# soldering.net
KiCad netlist of a schematic drawn in Altium Designer
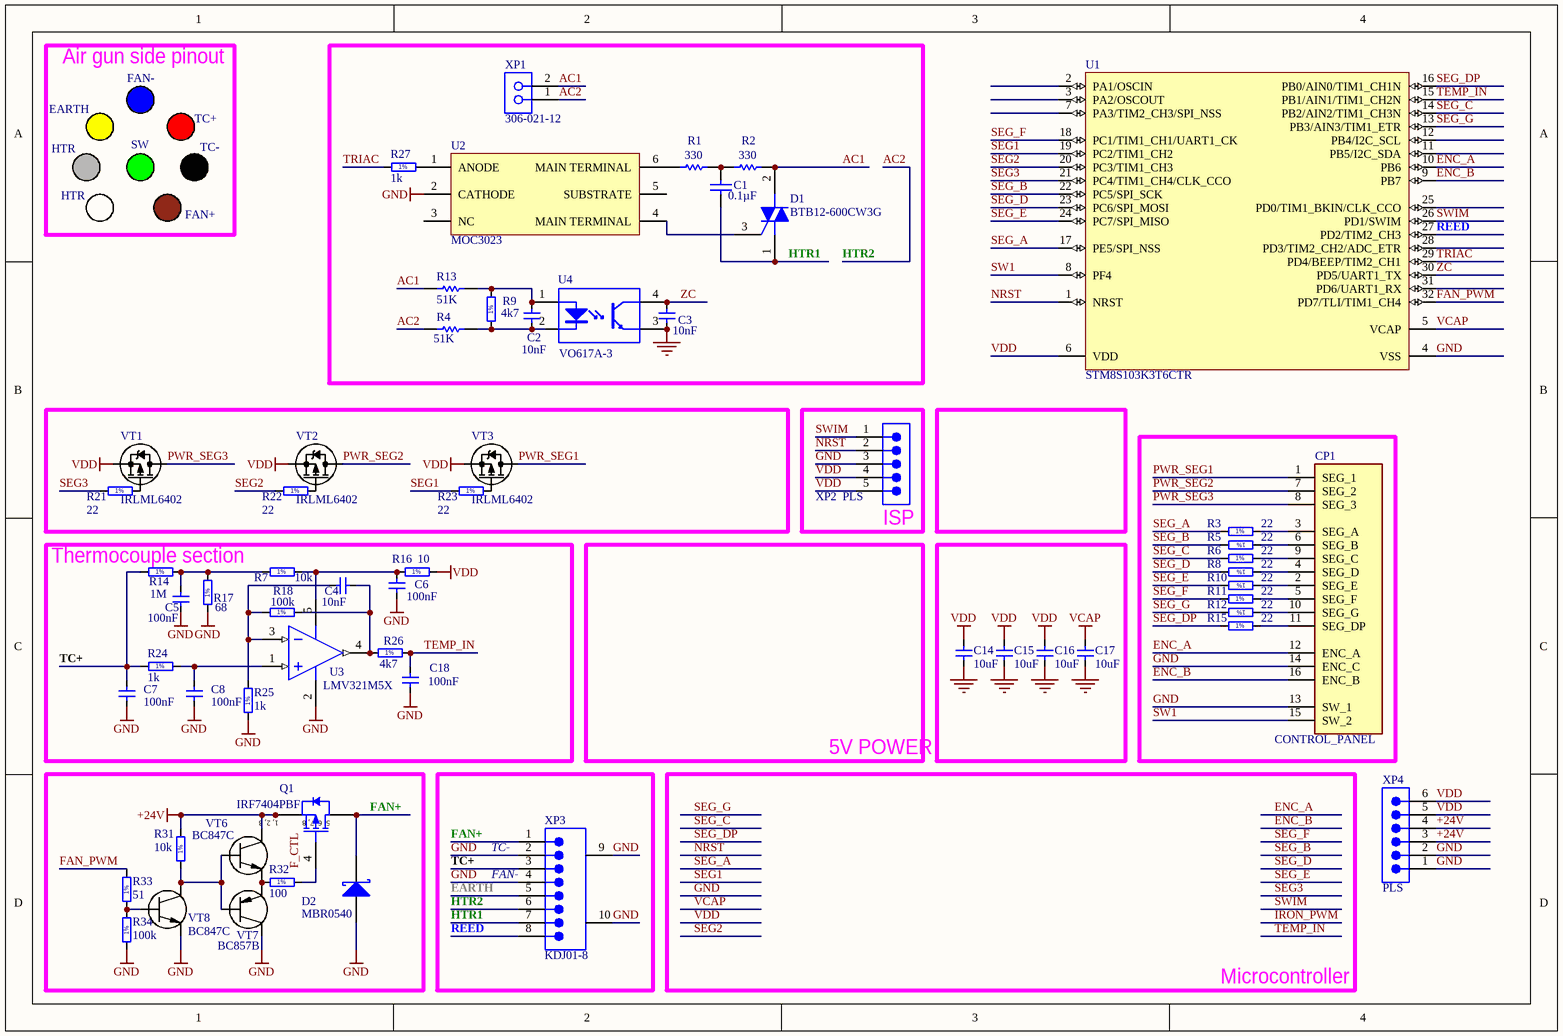
[diagram p0: soldering.SchDoc]

(export (version "E")
  (design (tool "Eeschema 10.0.6"))
  (components
    (comp (ref "C1")
      (value "A104M15X7RF5TAA")
      (footprint "CAPA55-380X260")
      (fields
        (field (name "MANUFACTURER") "Vishay")
        (field (name "CAPACITANCE") "0.1µF")
        (field (name "TOLERANCE") "±20%")
      )
      (libsource (lib "Altium Content Vault") (part "CAP-NP-2"))
    )
    (comp (ref "C2")
      (value "10nF")
      (footprint "CAP0805R")
      (fields
        (field (name "PART NUMBER") "CC0805_10NF_250V_10%_X7R")
        (field (name "VOLTAGE") "250V")
        (field (name "TOLERANCE") "±10%")
        (field (name "AUTHOR") "I. Kuznetsov")
      )
      (libsource (lib "Capacitor") (part "CAP_NON_POLAR"))
    )
    (comp (ref "C3")
      (value "10nF")
      (footprint "CAP0805R")
      (fields
        (field (name "PART NUMBER") "CC0805_10NF_250V_10%_X7R")
        (field (name "VOLTAGE") "250V")
        (field (name "TOLERANCE") "±10%")
        (field (name "AUTHOR") "I. Kuznetsov")
      )
      (libsource (lib "Capacitor") (part "CAP_NON_POLAR"))
    )
    (comp (ref "C4")
      (value "10nF")
      (footprint "CAP0805R")
      (fields
        (field (name "PART NUMBER") "CC0805_10NF_250V_10%_X7R")
        (field (name "VOLTAGE") "250V")
        (field (name "TOLERANCE") "±10%")
        (field (name "AUTHOR") "I. Kuznetsov")
      )
      (libsource (lib "Capacitor") (part "CAP_NON_POLAR"))
    )
    (comp (ref "C5")
      (value "100nF")
      (footprint "CAP0805R")
      (description "SMD 0805 Capacitor")
      (fields
        (field (name "PART NUMBER") "CC0805_100NF_50V_10%_X7R")
        (field (name "VOLTAGE") "50V")
        (field (name "AUTHOR") "I. Kuznetsov")
      )
      (libsource (lib "Capacitor") (part "CAP_NON_POLAR"))
    )
    (comp (ref "C6")
      (value "100nF")
      (footprint "CAP0805R")
      (description "SMD 0805 Capacitor")
      (fields
        (field (name "PART NUMBER") "CC0805_100NF_50V_10%_X7R")
        (field (name "VOLTAGE") "50V")
        (field (name "AUTHOR") "I. Kuznetsov")
      )
      (libsource (lib "Capacitor") (part "CAP_NON_POLAR"))
    )
    (comp (ref "C7")
      (value "100nF")
      (footprint "CAP0805R")
      (description "SMD 0805 Capacitor")
      (fields
        (field (name "PART NUMBER") "CC0805_100NF_50V_10%_X7R")
        (field (name "VOLTAGE") "50V")
        (field (name "AUTHOR") "I. Kuznetsov")
      )
      (libsource (lib "Capacitor") (part "CAP_NON_POLAR"))
    )
    (comp (ref "C8")
      (value "100nF")
      (footprint "CAP0805R")
      (description "SMD 0805 Capacitor")
      (fields
        (field (name "PART NUMBER") "CC0805_100NF_50V_10%_X7R")
        (field (name "VOLTAGE") "50V")
        (field (name "AUTHOR") "I. Kuznetsov")
      )
      (libsource (lib "Capacitor") (part "CAP_NON_POLAR"))
    )
    (comp (ref "C14")
      (value "10uF")
      (footprint "CAP0805R")
      (description "SMD 0805 Capacitor")
      (fields
        (field (name "PART NUMBER") "CC0805_10UF_10V_10%_X7R")
        (field (name "VOLTAGE") "10V")
        (field (name "AUTHOR") "I. Kuznetsov")
      )
      (libsource (lib "Capacitor") (part "CAP_NON_POLAR"))
    )
    (comp (ref "C15")
      (value "10uF")
      (footprint "CAP0805R")
      (description "SMD 0805 Capacitor")
      (fields
        (field (name "PART NUMBER") "CC0805_10UF_10V_10%_X7R")
        (field (name "VOLTAGE") "10V")
        (field (name "AUTHOR") "I. Kuznetsov")
      )
      (libsource (lib "Capacitor") (part "CAP_NON_POLAR"))
    )
    (comp (ref "C16")
      (value "10uF")
      (footprint "CAP0805R")
      (description "SMD 0805 Capacitor")
      (fields
        (field (name "PART NUMBER") "CC0805_10UF_10V_10%_X7R")
        (field (name "VOLTAGE") "10V")
        (field (name "AUTHOR") "I. Kuznetsov")
      )
      (libsource (lib "Capacitor") (part "CAP_NON_POLAR"))
    )
    (comp (ref "C17")
      (value "10uF")
      (footprint "CAP0805R")
      (description "SMD 0805 Capacitor")
      (fields
        (field (name "PART NUMBER") "CC0805_10UF_10V_10%_X7R")
        (field (name "VOLTAGE") "10V")
        (field (name "AUTHOR") "I. Kuznetsov")
      )
      (libsource (lib "Capacitor") (part "CAP_NON_POLAR"))
    )
    (comp (ref "C18")
      (value "100nF")
      (footprint "CAP0805R")
      (description "SMD 0805 Capacitor")
      (fields
        (field (name "PART NUMBER") "CC0805_100NF_50V_10%_X7R")
        (field (name "VOLTAGE") "50V")
        (field (name "AUTHOR") "I. Kuznetsov")
      )
      (libsource (lib "Capacitor") (part "CAP_NON_POLAR"))
    )
    (comp (ref "CP1")
      (value "CONTROL_PANEL")
      (footprint "CONTROL_PANEL")
      (libsource (lib "soldering") (part "CONTROL_PANEL"))
    )
    (comp (ref "D1")
      (value "BTB12-600CW3G")
      (footprint "ONSC-TO-220-3-221A-07")
      (description "Triacs, Silicon Bidirectional Thyristor, 3-Pin TO-220, Pb-Free, Tube")
      (fields (field (name "MANUFACTURER") "On Semiconductor"))
      (libsource (lib "Altium Content Vault") (part "ONSC-TRIAC-MT1MT2G-3"))
    )
    (comp (ref "D2")
      (value "MBR0540")
      (footprint "FAIR-SOD123-2_V")
      (description "Schottky Rectifier, 40 V, 0.5 A, 2-Pin SOD-123, RoHS, Tape and Reel")
      (fields (field (name "MANUFACTURER") "Fairchild"))
      (libsource (lib "Altium Content Vault") (part "DSKY-AK-2"))
    )
    (comp (ref "Q1")
      (value "IRF7404PBF")
      (footprint "INF-SOIC-8_V")
      (description "HEXFET(R) Power MOSFET, 6.7 A, 20 V, 8-Pin SOIC, RoHS, Tape and Reel")
      (fields (field (name "MANUFACTURER") "InfineonTechnologies"))
      (libsource (lib "Altium Content Vault") (part "PEMOS-SSSGDDDD-8"))
    )
    (comp (ref "R1")
      (value "MFR-25FBF52-1K")
      (footprint "RESA60-630X240")
      (description "Axial Resistor, 1 KOhm, +/- 1%, 250 mW, -55 to 155 degC, 2-Pin THD, RoHS, Bulk")
      (fields (field (name "TOLERANCE") "1%") (field (name "RESISTANCE") "330"))
      (libsource (lib "Altium Content Vault") (part "RES-2"))
    )
    (comp (ref "R2")
      (value "MFR-25FBF52-1K")
      (footprint "RESA60-630X240")
      (description "Axial Resistor, 1 KOhm, +/- 1%, 250 mW, -55 to 155 degC, 2-Pin THD, RoHS, Bulk")
      (fields (field (name "TOLERANCE") "1%") (field (name "RESISTANCE") "330"))
      (libsource (lib "Altium Content Vault") (part "RES-2"))
    )
    (comp (ref "R3")
      (value "22")
      (footprint "RES0805R")
      (fields
        (field (name "PART NUMBER") "R0805_22R_1%_0.125W_100PPM")
        (field (name "POWER") "0.125W")
        (field (name "TOLERANCE") "±1%")
        (field (name "AUTHOR") "CERN DEM JLC")
      )
      (libsource (lib "Resistor") (part "Resistor - 1%"))
    )
    (comp (ref "R4")
      (value "MFR-25FBF52-1K")
      (footprint "RESA60-630X240")
      (description "Axial Resistor, 1 KOhm, +/- 1%, 250 mW, -55 to 155 degC, 2-Pin THD, RoHS, Bulk")
      (fields (field (name "TOLERANCE") "1%") (field (name "RESISTANCE") "51K"))
      (libsource (lib "Altium Content Vault") (part "RES-2"))
    )
    (comp (ref "R5")
      (value "22")
      (footprint "RES0805R")
      (fields
        (field (name "PART NUMBER") "R0805_22R_1%_0.125W_100PPM")
        (field (name "POWER") "0.125W")
        (field (name "TOLERANCE") "±1%")
        (field (name "AUTHOR") "CERN DEM JLC")
      )
      (libsource (lib "Resistor") (part "Resistor - 1%"))
    )
    (comp (ref "R6")
      (value "22")
      (footprint "RES0805R")
      (fields
        (field (name "PART NUMBER") "R0805_22R_1%_0.125W_100PPM")
        (field (name "POWER") "0.125W")
        (field (name "TOLERANCE") "±1%")
        (field (name "AUTHOR") "CERN DEM JLC")
      )
      (libsource (lib "Resistor") (part "Resistor - 1%"))
    )
    (comp (ref "R7")
      (value "10k")
      (footprint "RES0805R")
      (fields
        (field (name "PART NUMBER") "R0805_10K_1%_0.125W_100PPM")
        (field (name "POWER") "0.125W")
        (field (name "TOLERANCE") "±1%")
        (field (name "AUTHOR") "CERN DEM JLC")
      )
      (libsource (lib "Resistor") (part "Resistor - 1%"))
    )
    (comp (ref "R8")
      (value "22")
      (footprint "RES0805R")
      (fields
        (field (name "PART NUMBER") "R0805_22R_1%_0.125W_100PPM")
        (field (name "POWER") "0.125W")
        (field (name "TOLERANCE") "±1%")
        (field (name "AUTHOR") "CERN DEM JLC")
      )
      (libsource (lib "Resistor") (part "Resistor - 1%"))
    )
    (comp (ref "R9")
      (value "4k7")
      (footprint "RES0805R")
      (fields
        (field (name "PART NUMBER") "R0805_4K7_1%_0.125W_100PPM")
        (field (name "POWER") "0.125W")
        (field (name "TOLERANCE") "±1%")
        (field (name "AUTHOR") "CERN DEM JLC")
      )
      (libsource (lib "Resistor") (part "Resistor - 1%"))
    )
    (comp (ref "R10")
      (value "22")
      (footprint "RES0805R")
      (fields
        (field (name "PART NUMBER") "R0805_22R_1%_0.125W_100PPM")
        (field (name "POWER") "0.125W")
        (field (name "TOLERANCE") "±1%")
        (field (name "AUTHOR") "CERN DEM JLC")
      )
      (libsource (lib "Resistor") (part "Resistor - 1%"))
    )
    (comp (ref "R11")
      (value "22")
      (footprint "RES0805R")
      (fields
        (field (name "PART NUMBER") "R0805_22R_1%_0.125W_100PPM")
        (field (name "POWER") "0.125W")
        (field (name "TOLERANCE") "±1%")
        (field (name "AUTHOR") "CERN DEM JLC")
      )
      (libsource (lib "Resistor") (part "Resistor - 1%"))
    )
    (comp (ref "R12")
      (value "22")
      (footprint "RES0805R")
      (fields
        (field (name "PART NUMBER") "R0805_22R_1%_0.125W_100PPM")
        (field (name "POWER") "0.125W")
        (field (name "TOLERANCE") "±1%")
        (field (name "AUTHOR") "CERN DEM JLC")
      )
      (libsource (lib "Resistor") (part "Resistor - 1%"))
    )
    (comp (ref "R13")
      (value "MFR-25FBF52-1K")
      (footprint "RESA60-630X240")
      (description "Axial Resistor, 1 KOhm, +/- 1%, 250 mW, -55 to 155 degC, 2-Pin THD, RoHS, Bulk")
      (fields (field (name "TOLERANCE") "1%") (field (name "RESISTANCE") "51K"))
      (libsource (lib "Altium Content Vault") (part "RES-2"))
    )
    (comp (ref "R14")
      (value "1M")
      (footprint "RES0805R")
      (fields
        (field (name "PART NUMBER") "R0805_1M_1%_0.125W_100PPM")
        (field (name "POWER") "0.125W")
        (field (name "TOLERANCE") "±1%")
        (field (name "AUTHOR") "CERN DEM JLC")
      )
      (libsource (lib "Resistor") (part "Resistor - 1%"))
    )
    (comp (ref "R15")
      (value "22")
      (footprint "RES0805R")
      (fields
        (field (name "PART NUMBER") "R0805_22R_1%_0.125W_100PPM")
        (field (name "POWER") "0.125W")
        (field (name "TOLERANCE") "±1%")
        (field (name "AUTHOR") "CERN DEM JLC")
      )
      (libsource (lib "Resistor") (part "Resistor - 1%"))
    )
    (comp (ref "R16")
      (value "10")
      (footprint "RES0805R")
      (fields
        (field (name "PART NUMBER") "R0805_10R_1%_0.125W_200PPM")
        (field (name "POWER") "0.125W")
        (field (name "TOLERANCE") "±1%")
        (field (name "AUTHOR") "CERN DEM JLC")
      )
      (libsource (lib "Resistor") (part "Resistor - 1%"))
    )
    (comp (ref "R17")
      (value "68")
      (footprint "RES0805R")
      (fields
        (field (name "PART NUMBER") "R0805_68R_1%_0.125W_100PPM")
        (field (name "POWER") "0.125W")
        (field (name "TOLERANCE") "±1%")
        (field (name "AUTHOR") "CERN DEM JLC")
      )
      (libsource (lib "Resistor") (part "Resistor - 1%"))
    )
    (comp (ref "R18")
      (value "100k")
      (footprint "RES0805R")
      (fields
        (field (name "PART NUMBER") "R0805_100K_1%_0.125W_100PPM")
        (field (name "POWER") "0.125W")
        (field (name "TOLERANCE") "±1%")
        (field (name "AUTHOR") "CERN DEM JLC")
      )
      (libsource (lib "Resistor") (part "Resistor - 1%"))
    )
    (comp (ref "R21")
      (value "22")
      (footprint "RES0805R")
      (fields
        (field (name "PART NUMBER") "R0805_22R_1%_0.125W_100PPM")
        (field (name "POWER") "0.125W")
        (field (name "TOLERANCE") "±1%")
        (field (name "AUTHOR") "CERN DEM JLC")
      )
      (libsource (lib "Resistor") (part "Resistor - 1%"))
    )
    (comp (ref "R22")
      (value "22")
      (footprint "RES0805R")
      (fields
        (field (name "PART NUMBER") "R0805_22R_1%_0.125W_100PPM")
        (field (name "POWER") "0.125W")
        (field (name "TOLERANCE") "±1%")
        (field (name "AUTHOR") "CERN DEM JLC")
      )
      (libsource (lib "Resistor") (part "Resistor - 1%"))
    )
    (comp (ref "R23")
      (value "22")
      (footprint "RES0805R")
      (fields
        (field (name "PART NUMBER") "R0805_22R_1%_0.125W_100PPM")
        (field (name "POWER") "0.125W")
        (field (name "TOLERANCE") "±1%")
        (field (name "AUTHOR") "CERN DEM JLC")
      )
      (libsource (lib "Resistor") (part "Resistor - 1%"))
    )
    (comp (ref "R24")
      (value "1k")
      (footprint "RES0805R")
      (fields
        (field (name "PART NUMBER") "R0805_1K_1%_0.125W_100PPM")
        (field (name "POWER") "0.125W")
        (field (name "TOLERANCE") "±1%")
        (field (name "AUTHOR") "CERN DEM JLC")
      )
      (libsource (lib "Resistor") (part "Resistor - 1%"))
    )
    (comp (ref "R25")
      (value "1k")
      (footprint "RES0805R")
      (fields
        (field (name "PART NUMBER") "R0805_1K_1%_0.125W_100PPM")
        (field (name "POWER") "0.125W")
        (field (name "TOLERANCE") "±1%")
        (field (name "AUTHOR") "CERN DEM JLC")
      )
      (libsource (lib "Resistor") (part "Resistor - 1%"))
    )
    (comp (ref "R26")
      (value "4k7")
      (footprint "RES0805R")
      (fields
        (field (name "PART NUMBER") "R0805_4K7_1%_0.125W_100PPM")
        (field (name "POWER") "0.125W")
        (field (name "TOLERANCE") "±1%")
        (field (name "AUTHOR") "CERN DEM JLC")
      )
      (libsource (lib "Resistor") (part "Resistor - 1%"))
    )
    (comp (ref "R27")
      (value "1k")
      (footprint "RES0805R")
      (fields
        (field (name "PART NUMBER") "R0805_1K_1%_0.125W_100PPM")
        (field (name "POWER") "0.125W")
        (field (name "TOLERANCE") "±1%")
        (field (name "AUTHOR") "CERN DEM JLC")
      )
      (libsource (lib "Resistor") (part "Resistor - 1%"))
    )
    (comp (ref "R31")
      (value "10k")
      (footprint "RES0805R")
      (fields
        (field (name "PART NUMBER") "R0805_10K_1%_0.125W_100PPM")
        (field (name "POWER") "0.125W")
        (field (name "TOLERANCE") "±1%")
        (field (name "AUTHOR") "CERN DEM JLC")
      )
      (libsource (lib "Resistor") (part "Resistor - 1%"))
    )
    (comp (ref "R32")
      (value "100")
      (footprint "RES0805R")
      (fields
        (field (name "PART NUMBER") "R0805_100R_1%_0.125W_100PPM")
        (field (name "POWER") "0.125W")
        (field (name "TOLERANCE") "±1%")
        (field (name "AUTHOR") "CERN DEM JLC")
      )
      (libsource (lib "Resistor") (part "Resistor - 1%"))
    )
    (comp (ref "R33")
      (value "51")
      (footprint "RES0805R")
      (fields
        (field (name "PART NUMBER") "R0805_51R_1%_0.125W_100PPM")
        (field (name "POWER") "0.125W")
        (field (name "TOLERANCE") "±1%")
        (field (name "AUTHOR") "CERN DEM JLC")
      )
      (libsource (lib "Resistor") (part "Resistor - 1%"))
    )
    (comp (ref "R34")
      (value "100k")
      (footprint "RES0805R")
      (fields
        (field (name "PART NUMBER") "R0805_100K_1%_0.125W_100PPM")
        (field (name "POWER") "0.125W")
        (field (name "TOLERANCE") "±1%")
        (field (name "AUTHOR") "CERN DEM JLC")
      )
      (libsource (lib "Resistor") (part "Resistor - 1%"))
    )
    (comp (ref "U1")
      (value "STM8S103K3T6CTR")
      (footprint "STM-LQFP32_L")
      (description "STM8S 8-bit MCU, 8 kB Flash, 1 kB Internal RAM, -40 to 85 degC, 32-Pin LQFP, Tape and Reel")
      (fields (field (name "MANUFACTURER") "STMicroelectronics"))
      (libsource (lib "Altium Content Vault") (part "STM-STM8S103-T-32"))
    )
    (comp (ref "U2")
      (value "MOC3023")
      (footprint "LTST-DIP-6")
      (description "Optocoupler Triac, 50 mA, -40 to 100 degC, 6-Pin DIP, RoHS, Tube")
      (fields (field (name "MANUFACTURER") "Lite-On-Inc."))
      (libsource (lib "Altium Content Vault") (part "LTST-MOC3063-DIP-6"))
    )
    (comp (ref "U3")
      (value "LMV321M5X")
      (footprint "DBV0005A_N")
      (description "General Purpose, Low Voltage, Rail-to-Rail Output Operational Amplifiers, 5-pin SOT-23")
      (fields (field (name "MANUFACTURER") "Texas Instruments"))
      (libsource (lib "Altium Content Vault") (part "AMP-OPA-LMV551-5"))
    )
    (comp (ref "U4")
      (value "VO617A-3")
      (footprint "VISH-DIP-4")
      (fields (field (name "MANUFACTURER") "Vishay/Semiconductor"))
      (libsource (lib "Altium Content Vault") (part "OPTO-AKEC-4"))
    )
    (comp (ref "VT1")
      (value "IRLML6402")
      (footprint "SOT23")
      (fields (field (name "AUTHOR") "I. Kuznetsov"))
      (libsource (lib "IC And Semiconductor") (part "P_CH_MOSFET"))
    )
    (comp (ref "VT2")
      (value "IRLML6402")
      (footprint "SOT23")
      (fields (field (name "AUTHOR") "I. Kuznetsov"))
      (libsource (lib "IC And Semiconductor") (part "P_CH_MOSFET"))
    )
    (comp (ref "VT3")
      (value "IRLML6402")
      (footprint "SOT23")
      (fields (field (name "AUTHOR") "I. Kuznetsov"))
      (libsource (lib "IC And Semiconductor") (part "P_CH_MOSFET"))
    )
    (comp (ref "VT6")
      (value "BC847C")
      (footprint "SOT23")
      (fields (field (name "AUTHOR") "I. Kuznetsov"))
      (libsource (lib "IC And Semiconductor") (part "NPN_BIPOLAR_SOT23"))
    )
    (comp (ref "VT7")
      (value "BC857B")
      (footprint "SOT23")
      (fields (field (name "AUTHOR") "I. Kuznetsov"))
      (libsource (lib "IC And Semiconductor") (part "PNP_BIPOLAR"))
    )
    (comp (ref "VT8")
      (value "BC847C")
      (footprint "SOT23")
      (fields (field (name "AUTHOR") "I. Kuznetsov"))
      (libsource (lib "IC And Semiconductor") (part "NPN_BIPOLAR_SOT23"))
    )
    (comp (ref "XP1")
      (value "306-021-12")
      (footprint "306-021-12")
      (libsource (lib "Connector") (part "CN_02S_1W"))
    )
    (comp (ref "XP2")
      (value "PLS")
      (footprint "PLS-05")
      (fields (field (name "PART NUMBER") "PLS-05") (field (name "MANUFACTURER") "AUK"))
      (libsource (lib "Connector") (part "CN_05P_1W"))
    )
    (comp (ref "XP3") (value "KDJ01-8") (footprint "KDJ01-8") (libsource (lib "Connector") (part "KDJ01-8")))
    (comp (ref "XP4")
      (value "PLS")
      (footprint "PLS-06")
      (fields (field (name "PART NUMBER") "PLS-06") (field (name "MANUFACTURER") "AUK"))
      (libsource (lib "Connector") (part "CN_06P_1W"))
    )
  )
  (nets
    (net (code "1") (name "+24V") (class "Default")
      (node (ref "Q1") (pin "1") (pinfunction "S_1") (pintype "passive"))
      (node (ref "Q1") (pin "2") (pinfunction "S_2") (pintype "passive"))
      (node (ref "Q1") (pin "3") (pinfunction "S_3") (pintype "passive"))
      (node (ref "R31") (pin "2") (pinfunction "2_2") (pintype "passive"))
      (node (ref "VT6") (pin "3") (pinfunction "C_3") (pintype "passive"))
      (node (ref "XP4") (pin "3") (pinfunction "3_3") (pintype "passive"))
      (node (ref "XP4") (pin "4") (pinfunction "4_4") (pintype "passive"))
    )
    (net (code "2") (name "/AC1") (class "Default")
      (node (ref "D1") (pin "2") (pinfunction "MT2_2") (pintype "passive"))
      (node (ref "R13") (pin "1") (pinfunction "1_1") (pintype "passive"))
      (node (ref "R2") (pin "2") (pinfunction "2_2") (pintype "passive"))
      (node (ref "XP1") (pin "2") (pinfunction "2_2") (pintype "passive"))
    )
    (net (code "3") (name "/AC2") (class "Default")
      (node (ref "R4") (pin "1") (pinfunction "1_1") (pintype "passive"))
      (node (ref "XP1") (pin "1") (pinfunction "1_1") (pintype "passive"))
      (node (ref "XP3") (pin "6") (pinfunction "6_6") (pintype "passive"))
    )
    (net (code "4") (name "/EARTH") (class "Default")
      (node (ref "XP3") (pin "5") (pinfunction "5_5") (pintype "passive"))
    )
    (net (code "5") (name "/ENC_A") (class "Default")
      (node (ref "CP1") (pin "12") (pinfunction "ENC_A_12") (pintype "passive"))
      (node (ref "U1") (pin "10") (pinfunction "PB6_10") (pintype "bidirectional"))
    )
    (net (code "6") (name "/ENC_B") (class "Default")
      (node (ref "CP1") (pin "16") (pinfunction "ENC_B_16") (pintype "passive"))
      (node (ref "U1") (pin "9") (pinfunction "PB7_9") (pintype "bidirectional"))
    )
    (net (code "7") (name "/FAN+") (class "Default")
      (node (ref "D2") (pin "2") (pinfunction "K_2") (pintype "passive"))
      (node (ref "Q1") (pin "5") (pinfunction "D_5") (pintype "passive"))
      (node (ref "Q1") (pin "6") (pinfunction "D_6") (pintype "passive"))
      (node (ref "Q1") (pin "7") (pinfunction "D_7") (pintype "passive"))
      (node (ref "Q1") (pin "8") (pinfunction "D_8") (pintype "passive"))
      (node (ref "XP3") (pin "1") (pinfunction "1_1") (pintype "passive"))
    )
    (net (code "8") (name "/FAN_PWM") (class "Default")
      (node (ref "R33") (pin "2") (pinfunction "2_2") (pintype "passive"))
      (node (ref "U1") (pin "32") (pinfunction "PD7/TLI/TIM1_CH4_32") (pintype "bidirectional"))
    )
    (net (code "10") (name "/HTR1") (class "Default")
      (node (ref "C1") (pin "1") (pinfunction "1_1") (pintype "passive"))
      (node (ref "D1") (pin "1") (pinfunction "MT1_1") (pintype "passive"))
      (node (ref "XP3") (pin "7") (pinfunction "7_7") (pintype "passive"))
    )
    (net (code "12") (name "/NRST") (class "Default")
      (node (ref "U1") (pin "1") (pinfunction "NRST_1") (pintype "bidirectional"))
      (node (ref "XP2") (pin "2") (pinfunction "2_2") (pintype "passive"))
    )
    (net (code "13") (name "/PWR_SEG1") (class "Default")
      (node (ref "CP1") (pin "1") (pinfunction "SEG_1_1") (pintype "passive"))
      (node (ref "VT3") (pin "3") (pinfunction "D_3") (pintype "passive"))
    )
    (net (code "14") (name "/PWR_SEG2") (class "Default")
      (node (ref "CP1") (pin "7") (pinfunction "SEG_2_7") (pintype "passive"))
      (node (ref "VT2") (pin "3") (pinfunction "D_3") (pintype "passive"))
    )
    (net (code "15") (name "/PWR_SEG3") (class "Default")
      (node (ref "CP1") (pin "8") (pinfunction "SEG_3_8") (pintype "passive"))
      (node (ref "VT1") (pin "3") (pinfunction "D_3") (pintype "passive"))
    )
    (net (code "16") (name "/REED") (class "Default")
      (node (ref "U1") (pin "27") (pinfunction "PD2/TIM2_CH3_27") (pintype "bidirectional"))
      (node (ref "XP3") (pin "8") (pinfunction "8_8") (pintype "passive"))
    )
    (net (code "17") (name "/SEG1") (class "Default")
      (node (ref "R23") (pin "1") (pinfunction "1_1") (pintype "passive"))
      (node (ref "U1") (pin "19") (pinfunction "PC2/TIM1_CH2_19") (pintype "bidirectional"))
    )
    (net (code "18") (name "/SEG2") (class "Default")
      (node (ref "R22") (pin "1") (pinfunction "1_1") (pintype "passive"))
      (node (ref "U1") (pin "20") (pinfunction "PC3/TIM1_CH3_20") (pintype "bidirectional"))
    )
    (net (code "19") (name "/SEG3") (class "Default")
      (node (ref "R21") (pin "1") (pinfunction "1_1") (pintype "passive"))
      (node (ref "U1") (pin "21") (pinfunction "PC4/TIM1_CH4/CLK_CCO_21") (pintype "bidirectional"))
    )
    (net (code "20") (name "/SEG_A") (class "Default")
      (node (ref "R3") (pin "1") (pinfunction "1_1") (pintype "passive"))
      (node (ref "U1") (pin "17") (pinfunction "PE5/SPI_NSS_17") (pintype "bidirectional"))
    )
    (net (code "21") (name "/SEG_B") (class "Default")
      (node (ref "R5") (pin "2") (pinfunction "2_2") (pintype "passive"))
      (node (ref "U1") (pin "22") (pinfunction "PC5/SPI_SCK_22") (pintype "bidirectional"))
    )
    (net (code "22") (name "/SEG_C") (class "Default")
      (node (ref "R6") (pin "1") (pinfunction "1_1") (pintype "passive"))
      (node (ref "U1") (pin "14") (pinfunction "PB2/AIN2/TIM1_CH3N_14") (pintype "bidirectional"))
    )
    (net (code "23") (name "/SEG_D") (class "Default")
      (node (ref "R8") (pin "2") (pinfunction "2_2") (pintype "passive"))
      (node (ref "U1") (pin "23") (pinfunction "PC6/SPI_MOSI_23") (pintype "bidirectional"))
    )
    (net (code "24") (name "/SEG_DP") (class "Default")
      (node (ref "R15") (pin "1") (pinfunction "1_1") (pintype "passive"))
      (node (ref "U1") (pin "16") (pinfunction "PB0/AIN0/TIM1_CH1N_16") (pintype "bidirectional"))
    )
    (net (code "25") (name "/SEG_E") (class "Default")
      (node (ref "R10") (pin "2") (pinfunction "2_2") (pintype "passive"))
      (node (ref "U1") (pin "24") (pinfunction "PC7/SPI_MISO_24") (pintype "bidirectional"))
    )
    (net (code "26") (name "/SEG_F") (class "Default")
      (node (ref "R11") (pin "1") (pinfunction "1_1") (pintype "passive"))
      (node (ref "U1") (pin "18") (pinfunction "PC1/TIM1_CH1/UART1_CK_18") (pintype "bidirectional"))
    )
    (net (code "27") (name "/SEG_G") (class "Default")
      (node (ref "R12") (pin "2") (pinfunction "2_2") (pintype "passive"))
      (node (ref "U1") (pin "13") (pinfunction "PB3/AIN3/TIM1_ETR_13") (pintype "bidirectional"))
    )
    (net (code "28") (name "/SW1") (class "Default")
      (node (ref "CP1") (pin "15") (pinfunction "SW_2_15") (pintype "passive"))
      (node (ref "U1") (pin "8") (pinfunction "PF4_8") (pintype "bidirectional"))
    )
    (net (code "29") (name "/SWIM") (class "Default")
      (node (ref "U1") (pin "26") (pinfunction "PD1/SWIM_26") (pintype "bidirectional"))
      (node (ref "XP2") (pin "1") (pinfunction "1_1") (pintype "passive"))
    )
    (net (code "30") (name "/TC+") (class "Default")
      (node (ref "C7") (pin "2") (pinfunction "2_2") (pintype "passive"))
      (node (ref "R14") (pin "1") (pinfunction "1_1") (pintype "passive"))
      (node (ref "R24") (pin "1") (pinfunction "1_1") (pintype "passive"))
      (node (ref "XP3") (pin "3") (pinfunction "3_3") (pintype "passive"))
    )
    (net (code "31") (name "/TEMP_IN") (class "Default")
      (node (ref "C18") (pin "2") (pinfunction "2_2") (pintype "passive"))
      (node (ref "R26") (pin "2") (pinfunction "2_2") (pintype "passive"))
      (node (ref "U1") (pin "15") (pinfunction "PB1/AIN1/TIM1_CH2N_15") (pintype "bidirectional"))
    )
    (net (code "32") (name "/TRIAC") (class "Default")
      (node (ref "R27") (pin "1") (pinfunction "1_1") (pintype "passive"))
      (node (ref "U1") (pin "29") (pinfunction "PD4/BEEP/TIM2_CH1_29") (pintype "bidirectional"))
    )
    (net (code "33") (name "/ZC") (class "Default")
      (node (ref "C3") (pin "2") (pinfunction "2_2") (pintype "passive"))
      (node (ref "U1") (pin "30") (pinfunction "PD5/UART1_TX_30") (pintype "bidirectional"))
      (node (ref "U4") (pin "4") (pinfunction "COLLECTOR_4") (pintype "passive"))
    )
    (net (code "34") (name "GND") (class "Default")
      (node (ref "C14") (pin "1") (pinfunction "1_1") (pintype "passive"))
      (node (ref "C15") (pin "1") (pinfunction "1_1") (pintype "passive"))
      (node (ref "C16") (pin "1") (pinfunction "1_1") (pintype "passive"))
      (node (ref "C17") (pin "1") (pinfunction "1_1") (pintype "passive"))
      (node (ref "C18") (pin "1") (pinfunction "1_1") (pintype "passive"))
      (node (ref "C3") (pin "1") (pinfunction "1_1") (pintype "passive"))
      (node (ref "C5") (pin "1") (pinfunction "1_1") (pintype "passive"))
      (node (ref "C6") (pin "1") (pinfunction "1_1") (pintype "passive"))
      (node (ref "C7") (pin "1") (pinfunction "1_1") (pintype "passive"))
      (node (ref "C8") (pin "1") (pinfunction "1_1") (pintype "passive"))
      (node (ref "CP1") (pin "13") (pinfunction "SW_1_13") (pintype "passive"))
      (node (ref "CP1") (pin "14") (pinfunction "ENC_C_14") (pintype "passive"))
      (node (ref "D2") (pin "1") (pinfunction "A_1") (pintype "passive"))
      (node (ref "R17") (pin "1") (pinfunction "1_1") (pintype "passive"))
      (node (ref "R25") (pin "1") (pinfunction "1_1") (pintype "passive"))
      (node (ref "R34") (pin "1") (pinfunction "1_1") (pintype "passive"))
      (node (ref "U1") (pin "4") (pinfunction "VSS_4") (pintype "power_in"))
      (node (ref "U2") (pin "2") (pinfunction "CATHODE_2") (pintype "passive"))
      (node (ref "U3") (pin "2") (pinfunction "V-_2") (pintype "power_in"))
      (node (ref "U4") (pin "3") (pinfunction "EMITTER_3") (pintype "passive"))
      (node (ref "VT7") (pin "3") (pinfunction "C_3") (pintype "passive"))
      (node (ref "VT8") (pin "2") (pinfunction "E_2") (pintype "passive"))
      (node (ref "XP2") (pin "3") (pinfunction "3_3") (pintype "passive"))
      (node (ref "XP3") (pin "10") (pinfunction "10_10") (pintype "passive"))
      (node (ref "XP3") (pin "2") (pinfunction "2_2") (pintype "passive"))
      (node (ref "XP3") (pin "4") (pinfunction "4_4") (pintype "passive"))
      (node (ref "XP3") (pin "9") (pinfunction "9_9") (pintype "passive"))
      (node (ref "XP4") (pin "1") (pinfunction "1_1") (pintype "passive"))
      (node (ref "XP4") (pin "2") (pinfunction "2_2") (pintype "passive"))
    )
    (net (code "35") (name "Net-(C1-Pad2)") (class "Default")
      (node (ref "C1") (pin "2") (pinfunction "2_2") (pintype "passive"))
      (node (ref "R1") (pin "2") (pinfunction "2_2") (pintype "passive"))
      (node (ref "R2") (pin "1") (pinfunction "1_1") (pintype "passive"))
    )
    (net (code "36") (name "Net-(C5-Pad2)") (class "Default")
      (node (ref "C5") (pin "2") (pinfunction "2_2") (pintype "passive"))
      (node (ref "R14") (pin "2") (pinfunction "2_2") (pintype "passive"))
      (node (ref "R17") (pin "2") (pinfunction "2_2") (pintype "passive"))
      (node (ref "R7") (pin "1") (pinfunction "1_1") (pintype "passive"))
    )
    (net (code "37") (name "Net-(CP1-SEG_A)") (class "Default")
      (node (ref "CP1") (pin "3") (pinfunction "SEG_A_3") (pintype "passive"))
      (node (ref "R3") (pin "2") (pinfunction "2_2") (pintype "passive"))
    )
    (net (code "38") (name "Net-(CP1-SEG_B)") (class "Default")
      (node (ref "CP1") (pin "6") (pinfunction "SEG_B_6") (pintype "passive"))
      (node (ref "R5") (pin "1") (pinfunction "1_1") (pintype "passive"))
    )
    (net (code "39") (name "Net-(CP1-SEG_C)") (class "Default")
      (node (ref "CP1") (pin "9") (pinfunction "SEG_C_9") (pintype "passive"))
      (node (ref "R6") (pin "2") (pinfunction "2_2") (pintype "passive"))
    )
    (net (code "40") (name "Net-(CP1-SEG_D)") (class "Default")
      (node (ref "CP1") (pin "4") (pinfunction "SEG_D_4") (pintype "passive"))
      (node (ref "R8") (pin "1") (pinfunction "1_1") (pintype "passive"))
    )
    (net (code "41") (name "Net-(CP1-SEG_DP)") (class "Default")
      (node (ref "CP1") (pin "11") (pinfunction "SEG_DP_11") (pintype "passive"))
      (node (ref "R15") (pin "2") (pinfunction "2_2") (pintype "passive"))
    )
    (net (code "42") (name "Net-(CP1-SEG_E)") (class "Default")
      (node (ref "CP1") (pin "2") (pinfunction "SEG_E_2") (pintype "passive"))
      (node (ref "R10") (pin "1") (pinfunction "1_1") (pintype "passive"))
    )
    (net (code "43") (name "Net-(CP1-SEG_F)") (class "Default")
      (node (ref "CP1") (pin "5") (pinfunction "SEG_F_5") (pintype "passive"))
      (node (ref "R11") (pin "2") (pinfunction "2_2") (pintype "passive"))
    )
    (net (code "44") (name "Net-(CP1-SEG_G)") (class "Default")
      (node (ref "CP1") (pin "10") (pinfunction "SEG_G_10") (pintype "passive"))
      (node (ref "R12") (pin "1") (pinfunction "1_1") (pintype "passive"))
    )
    (net (code "45") (name "Net-(D1-G)") (class "Default")
      (node (ref "D1") (pin "3") (pinfunction "G_3") (pintype "passive"))
      (node (ref "U2") (pin "4") (pinfunction "MAIN_TERMINAL_4") (pintype "passive"))
    )
    (net (code "46") (name "Net-(Q1-G)") (class "Default")
      (node (ref "Q1") (pin "4") (pinfunction "G_4") (pintype "passive"))
      (node (ref "R32") (pin "2") (pinfunction "2_2") (pintype "passive"))
    )
    (net (code "47") (name "Net-(R1-Pad1)") (class "Default")
      (node (ref "R1") (pin "1") (pinfunction "1_1") (pintype "passive"))
      (node (ref "U2") (pin "6") (pinfunction "MAIN_TERMINAL_6") (pintype "passive"))
    )
    (net (code "48") (name "Net-(U2-ANODE)") (class "Default")
      (node (ref "R27") (pin "2") (pinfunction "2_2") (pintype "passive"))
      (node (ref "U2") (pin "1") (pinfunction "ANODE_1") (pintype "passive"))
    )
    (net (code "49") (name "Net-(U3-IN+)") (class "Default")
      (node (ref "C8") (pin "2") (pinfunction "2_2") (pintype "passive"))
      (node (ref "R24") (pin "2") (pinfunction "2_2") (pintype "passive"))
      (node (ref "U3") (pin "1") (pinfunction "IN+_1") (pintype "input"))
    )
    (net (code "50") (name "Net-(U3-IN-)") (class "Default")
      (node (ref "C4") (pin "2") (pinfunction "2_2") (pintype "passive"))
      (node (ref "R18") (pin "1") (pinfunction "1_1") (pintype "passive"))
      (node (ref "R25") (pin "2") (pinfunction "2_2") (pintype "passive"))
      (node (ref "U3") (pin "3") (pinfunction "IN-_3") (pintype "input"))
    )
    (net (code "51") (name "Net-(U3-OUT)") (class "Default")
      (node (ref "C4") (pin "1") (pinfunction "1_1") (pintype "passive"))
      (node (ref "R18") (pin "2") (pinfunction "2_2") (pintype "passive"))
      (node (ref "R26") (pin "1") (pinfunction "1_1") (pintype "passive"))
      (node (ref "U3") (pin "4") (pinfunction "OUT_4") (pintype "output"))
    )
    (net (code "52") (name "Net-(U3-V+)") (class "Default")
      (node (ref "C6") (pin "2") (pinfunction "2_2") (pintype "passive"))
      (node (ref "R16") (pin "1") (pinfunction "1_1") (pintype "passive"))
      (node (ref "R7") (pin "2") (pinfunction "2_2") (pintype "passive"))
      (node (ref "U3") (pin "5") (pinfunction "V+_5") (pintype "power_in"))
    )
    (net (code "53") (name "Net-(U4-ANODE)") (class "Default")
      (node (ref "C2") (pin "2") (pinfunction "2_2") (pintype "passive"))
      (node (ref "R13") (pin "2") (pinfunction "2_2") (pintype "passive"))
      (node (ref "R9") (pin "2") (pinfunction "2_2") (pintype "passive"))
      (node (ref "U4") (pin "1") (pinfunction "ANODE_1") (pintype "passive"))
    )
    (net (code "54") (name "Net-(U4-CATHODE)") (class "Default")
      (node (ref "C2") (pin "1") (pinfunction "1_1") (pintype "passive"))
      (node (ref "R4") (pin "2") (pinfunction "2_2") (pintype "passive"))
      (node (ref "R9") (pin "1") (pinfunction "1_1") (pintype "passive"))
      (node (ref "U4") (pin "2") (pinfunction "CATHODE_2") (pintype "passive"))
    )
    (net (code "55") (name "Net-(VT1-G)") (class "Default")
      (node (ref "R21") (pin "2") (pinfunction "2_2") (pintype "passive"))
      (node (ref "VT1") (pin "1") (pinfunction "G_1") (pintype "passive"))
    )
    (net (code "56") (name "Net-(VT2-G)") (class "Default")
      (node (ref "R22") (pin "2") (pinfunction "2_2") (pintype "passive"))
      (node (ref "VT2") (pin "1") (pinfunction "G_1") (pintype "passive"))
    )
    (net (code "57") (name "Net-(VT3-G)") (class "Default")
      (node (ref "R23") (pin "2") (pinfunction "2_2") (pintype "passive"))
      (node (ref "VT3") (pin "1") (pinfunction "G_1") (pintype "passive"))
    )
    (net (code "58") (name "Net-(VT6-B)") (class "Default")
      (node (ref "R31") (pin "1") (pinfunction "1_1") (pintype "passive"))
      (node (ref "VT6") (pin "1") (pinfunction "B_1") (pintype "passive"))
      (node (ref "VT7") (pin "1") (pinfunction "B_1") (pintype "passive"))
      (node (ref "VT8") (pin "3") (pinfunction "C_3") (pintype "passive"))
    )
    (net (code "59") (name "Net-(VT6-E)") (class "Default")
      (node (ref "R32") (pin "1") (pinfunction "1_1") (pintype "passive"))
      (node (ref "VT6") (pin "2") (pinfunction "E_2") (pintype "passive"))
      (node (ref "VT7") (pin "2") (pinfunction "E_2") (pintype "passive"))
    )
    (net (code "60") (name "Net-(VT8-B)") (class "Default")
      (node (ref "R33") (pin "1") (pinfunction "1_1") (pintype "passive"))
      (node (ref "R34") (pin "2") (pinfunction "2_2") (pintype "passive"))
      (node (ref "VT8") (pin "1") (pinfunction "B_1") (pintype "passive"))
    )
    (net (code "61") (name "VCAP") (class "Default")
      (node (ref "C17") (pin "2") (pinfunction "2_2") (pintype "passive"))
      (node (ref "U1") (pin "5") (pinfunction "VCAP_5") (pintype "passive"))
    )
    (net (code "62") (name "VDD") (class "Default")
      (node (ref "C14") (pin "2") (pinfunction "2_2") (pintype "passive"))
      (node (ref "C15") (pin "2") (pinfunction "2_2") (pintype "passive"))
      (node (ref "C16") (pin "2") (pinfunction "2_2") (pintype "passive"))
      (node (ref "R16") (pin "2") (pinfunction "2_2") (pintype "passive"))
      (node (ref "U1") (pin "6") (pinfunction "VDD_6") (pintype "power_in"))
      (node (ref "VT1") (pin "2") (pinfunction "S_2") (pintype "passive"))
      (node (ref "VT2") (pin "2") (pinfunction "S_2") (pintype "passive"))
      (node (ref "VT3") (pin "2") (pinfunction "S_2") (pintype "passive"))
      (node (ref "XP2") (pin "4") (pinfunction "4_4") (pintype "passive"))
      (node (ref "XP2") (pin "5") (pinfunction "5_5") (pintype "passive"))
      (node (ref "XP4") (pin "5") (pinfunction "5_5") (pintype "passive"))
      (node (ref "XP4") (pin "6") (pinfunction "6_6") (pintype "passive"))
    )
    (net (code "63") (name "unconnected-(U1-PA1{slash}OSCIN-Pad2)") (class "Default")
      (node (ref "U1") (pin "2") (pinfunction "PA1/OSCIN_2") (pintype "bidirectional"))
    )
    (net (code "64") (name "unconnected-(U1-PA2{slash}OSCOUT-Pad3)") (class "Default")
      (node (ref "U1") (pin "3") (pinfunction "PA2/OSCOUT_3") (pintype "bidirectional"))
    )
    (net (code "65") (name "unconnected-(U1-PA3{slash}TIM2_CH3{slash}SPI_NSS-Pad7)") (class "Default")
      (node (ref "U1") (pin "7") (pinfunction "PA3/TIM2_CH3/SPI_NSS_7") (pintype "bidirectional"))
    )
    (net (code "66") (name "unconnected-(U1-PB4{slash}I2C_SCL-Pad12)") (class "Default")
      (node (ref "U1") (pin "12") (pinfunction "PB4/I2C_SCL_12") (pintype "bidirectional"))
    )
    (net (code "67") (name "unconnected-(U1-PB5{slash}I2C_SDA-Pad11)") (class "Default")
      (node (ref "U1") (pin "11") (pinfunction "PB5/I2C_SDA_11") (pintype "bidirectional"))
    )
    (net (code "68") (name "unconnected-(U1-PD0{slash}TIM1_BKIN{slash}CLK_CCO-Pad25)") (class "Default")
      (node (ref "U1") (pin "25") (pinfunction "PD0/TIM1_BKIN/CLK_CCO_25") (pintype "bidirectional"))
    )
    (net (code "69") (name "unconnected-(U1-PD3{slash}TIM2_CH2{slash}ADC_ETR-Pad28)") (class "Default")
      (node (ref "U1") (pin "28") (pinfunction "PD3/TIM2_CH2/ADC_ETR_28") (pintype "bidirectional"))
    )
    (net (code "70") (name "unconnected-(U1-PD6{slash}UART1_RX-Pad31)") (class "Default")
      (node (ref "U1") (pin "31") (pinfunction "PD6/UART1_RX_31") (pintype "bidirectional"))
    )
    (net (code "71") (name "unconnected-(U2-NC-Pad3)") (class "Default")
      (node (ref "U2") (pin "3") (pinfunction "NC_3") (pintype "passive"))
    )
    (net (code "72") (name "unconnected-(U2-SUBSTRATE-Pad5)") (class "Default")
      (node (ref "U2") (pin "5") (pinfunction "SUBSTRATE_5") (pintype "passive"))
    )
  )
)
